# Rx_logic.net
KiCad netlist of a schematic drawn in Altium Designer
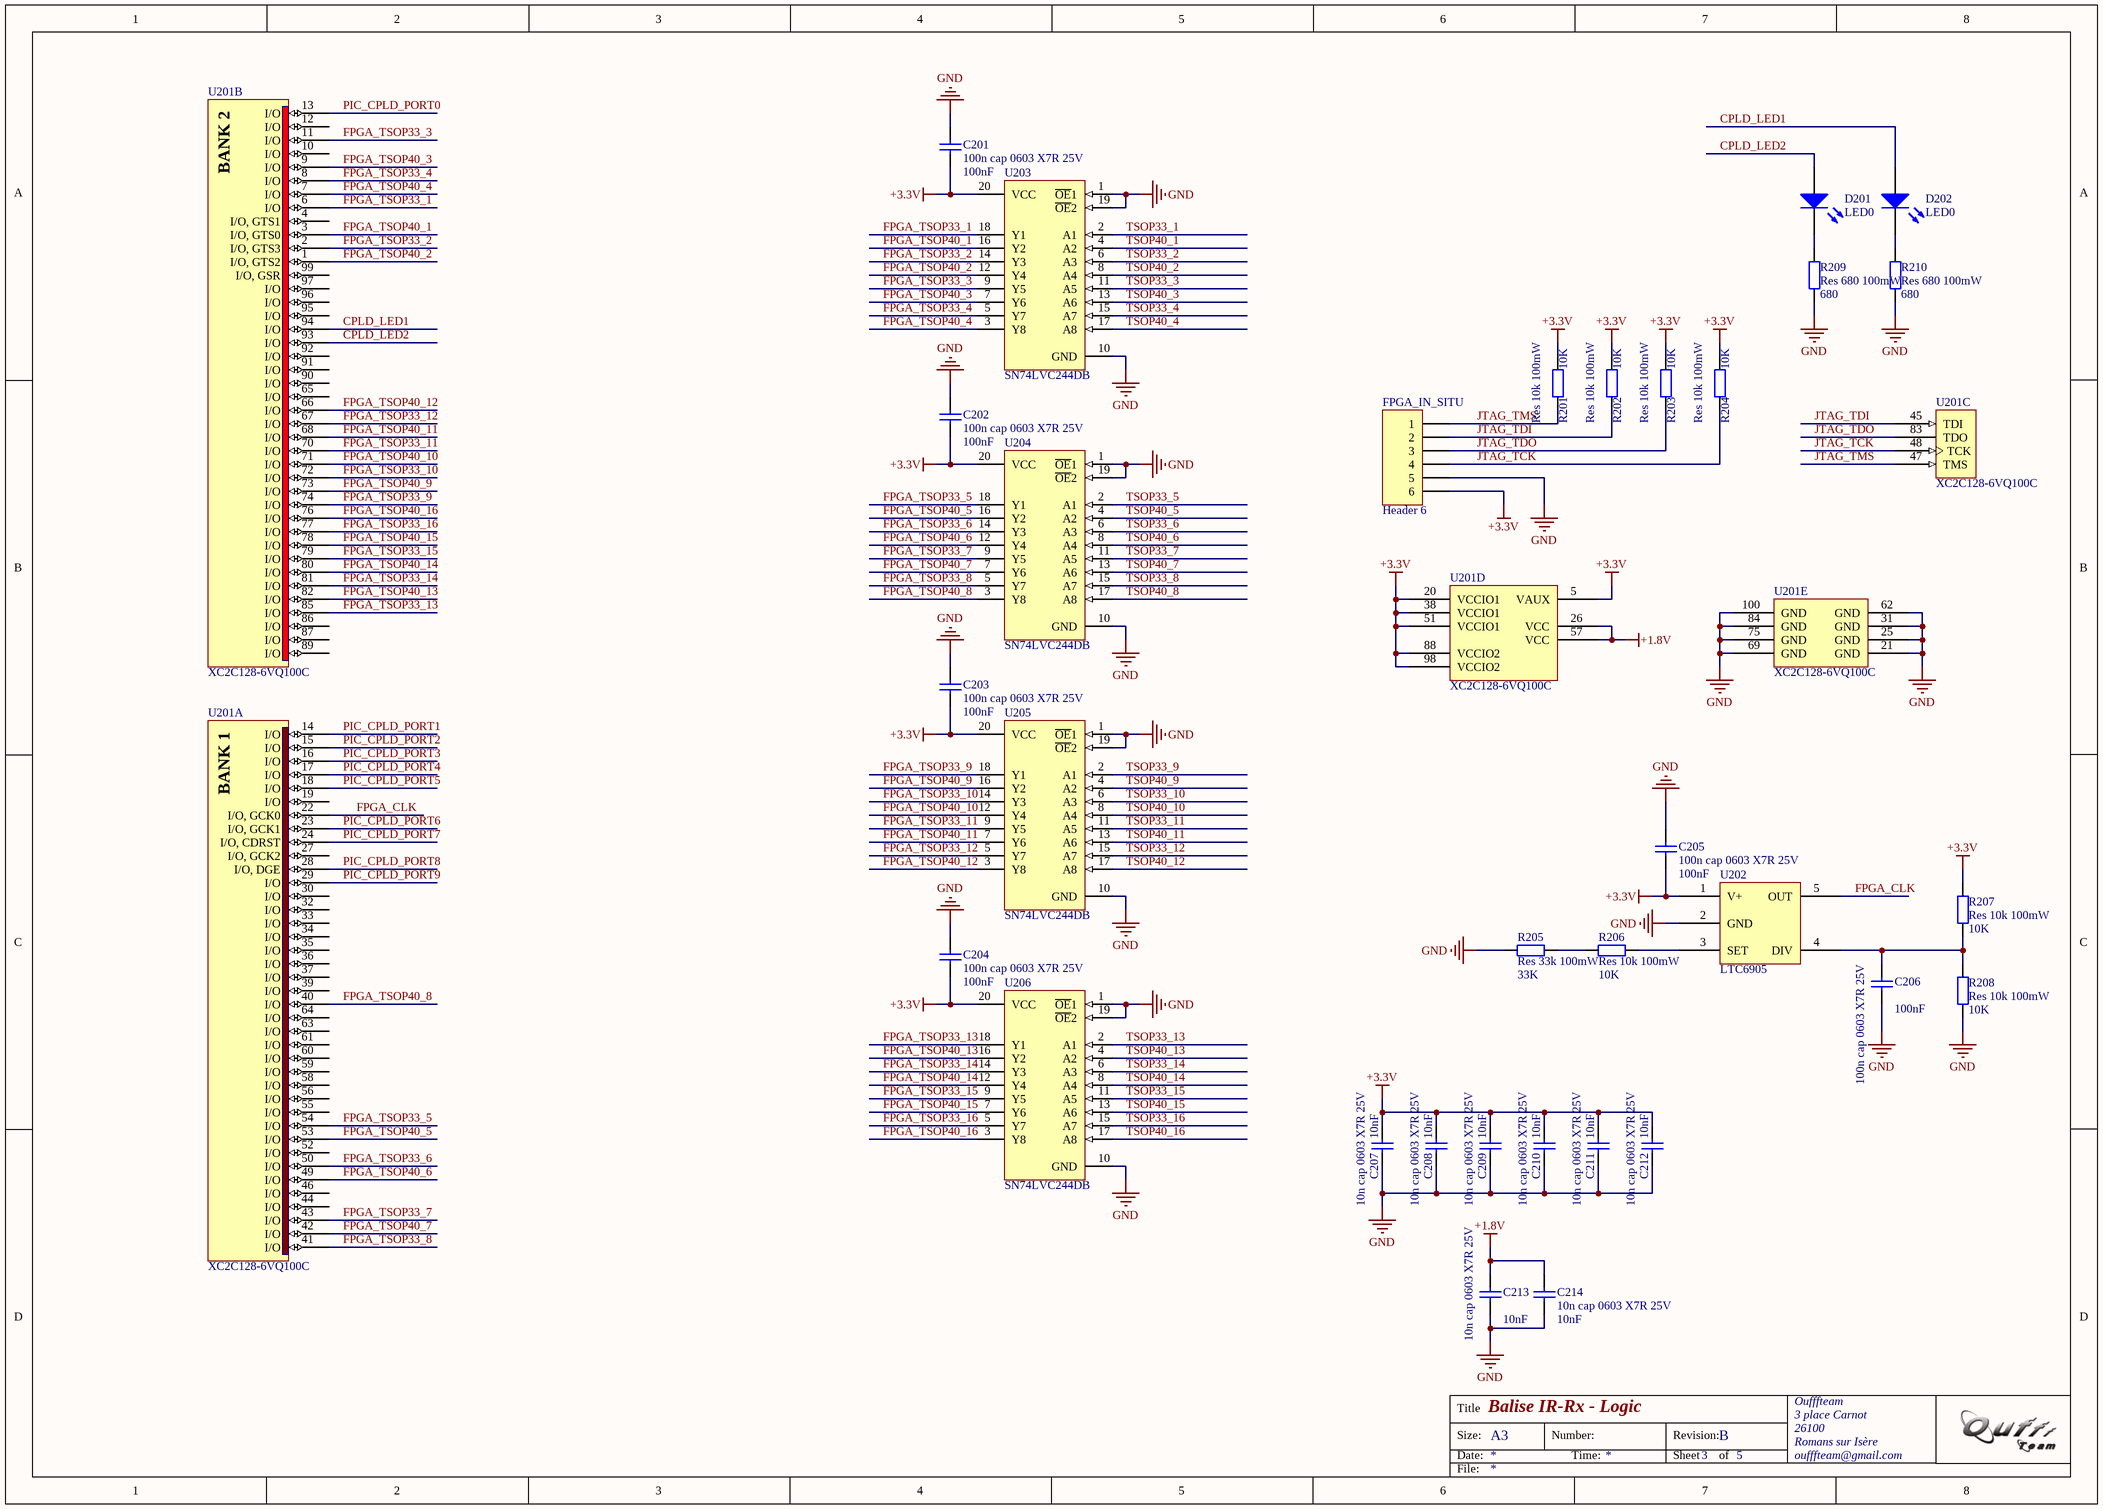
[diagram p0: Rx_logic.SchDoc]

(export (version "E")
  (design (tool "Eeschema 10.0.6"))
  (components
    (comp (ref "C201")
      (value "100n cap 0603 X7R 25V")
      (footprint "0603")
      (description "Capacitor")
      (fields (field (name "ALTIUM_VALUE") "100nF") (field (name "PUBLISHER") "Altium Limited"))
      (libsource (lib "Miscellaneous Devices") (part "Cap"))
    )
    (comp (ref "C202")
      (value "100n cap 0603 X7R 25V")
      (footprint "0603")
      (description "Capacitor")
      (fields (field (name "ALTIUM_VALUE") "100nF") (field (name "PUBLISHER") "Altium Limited"))
      (libsource (lib "Miscellaneous Devices") (part "Cap"))
    )
    (comp (ref "C203")
      (value "100n cap 0603 X7R 25V")
      (footprint "0603")
      (description "Capacitor")
      (fields (field (name "ALTIUM_VALUE") "100nF") (field (name "PUBLISHER") "Altium Limited"))
      (libsource (lib "Miscellaneous Devices") (part "Cap"))
    )
    (comp (ref "C204")
      (value "100n cap 0603 X7R 25V")
      (footprint "0603")
      (description "Capacitor")
      (fields (field (name "ALTIUM_VALUE") "100nF") (field (name "PUBLISHER") "Altium Limited"))
      (libsource (lib "Miscellaneous Devices") (part "Cap"))
    )
    (comp (ref "C205")
      (value "100n cap 0603 X7R 25V")
      (footprint "0603")
      (description "Capacitor")
      (fields (field (name "ALTIUM_VALUE") "100nF") (field (name "PUBLISHER") "Altium Limited"))
      (libsource (lib "Miscellaneous Devices") (part "Cap"))
    )
    (comp (ref "C206")
      (value "100n cap 0603 X7R 25V")
      (footprint "0603")
      (description "Capacitor")
      (fields (field (name "ALTIUM_VALUE") "100nF") (field (name "PUBLISHER") "Altium Limited"))
      (libsource (lib "Miscellaneous Devices") (part "Cap"))
    )
    (comp (ref "C207")
      (value "10n cap 0603 X7R 25V")
      (footprint "0603")
      (description "Capacitor")
      (fields (field (name "ALTIUM_VALUE") "10nF") (field (name "PUBLISHER") "Altium Limited"))
      (libsource (lib "Miscellaneous Devices") (part "Cap"))
    )
    (comp (ref "C208")
      (value "10n cap 0603 X7R 25V")
      (footprint "0603")
      (description "Capacitor")
      (fields (field (name "ALTIUM_VALUE") "10nF") (field (name "PUBLISHER") "Altium Limited"))
      (libsource (lib "Miscellaneous Devices") (part "Cap"))
    )
    (comp (ref "C209")
      (value "10n cap 0603 X7R 25V")
      (footprint "0603")
      (description "Capacitor")
      (fields (field (name "ALTIUM_VALUE") "10nF") (field (name "PUBLISHER") "Altium Limited"))
      (libsource (lib "Miscellaneous Devices") (part "Cap"))
    )
    (comp (ref "C210")
      (value "10n cap 0603 X7R 25V")
      (footprint "0603")
      (description "Capacitor")
      (fields (field (name "ALTIUM_VALUE") "10nF") (field (name "PUBLISHER") "Altium Limited"))
      (libsource (lib "Miscellaneous Devices") (part "Cap"))
    )
    (comp (ref "C211")
      (value "10n cap 0603 X7R 25V")
      (footprint "0603")
      (description "Capacitor")
      (fields (field (name "ALTIUM_VALUE") "10nF") (field (name "PUBLISHER") "Altium Limited"))
      (libsource (lib "Miscellaneous Devices") (part "Cap"))
    )
    (comp (ref "C212")
      (value "10n cap 0603 X7R 25V")
      (footprint "0603")
      (description "Capacitor")
      (fields (field (name "ALTIUM_VALUE") "10nF") (field (name "PUBLISHER") "Altium Limited"))
      (libsource (lib "Miscellaneous Devices") (part "Cap"))
    )
    (comp (ref "C213")
      (value "10n cap 0603 X7R 25V")
      (footprint "0603")
      (description "Capacitor")
      (fields (field (name "ALTIUM_VALUE") "10nF") (field (name "PUBLISHER") "Altium Limited"))
      (libsource (lib "Miscellaneous Devices") (part "Cap"))
    )
    (comp (ref "C214")
      (value "10n cap 0603 X7R 25V")
      (footprint "0603")
      (description "Capacitor")
      (fields (field (name "ALTIUM_VALUE") "10nF") (field (name "PUBLISHER") "Altium Limited"))
      (libsource (lib "Miscellaneous Devices") (part "Cap"))
    )
    (comp (ref "D201")
      (value "LED0")
      (footprint "0603")
      (description "0603 Led")
      (fields (field (name "PUBLISHER") "Altium Limited"))
      (libsource (lib "Miscellaneous Devices") (part "LED0"))
    )
    (comp (ref "D202")
      (value "LED0")
      (footprint "0603")
      (description "0603 Led")
      (fields (field (name "PUBLISHER") "Altium Limited"))
      (libsource (lib "Miscellaneous Devices") (part "LED0"))
    )
    (comp (ref "FPGA_IN_SITU")
      (value "Header 6")
      (footprint "HDR1X6")
      (description "Header, 6-Pin")
      (fields (field (name "PUBLISHER") "Altium Limited"))
      (libsource (lib "Miscellaneous Connectors") (part "Header 6"))
    )
    (comp (ref "R201")
      (value "Res 10k 100mW")
      (footprint "0603")
      (description "Resistor")
      (fields (field (name "ALTIUM_VALUE") "10K") (field (name "PUBLISHER") "Altium Limited"))
      (libsource (lib "Miscellaneous Devices") (part "Res2"))
    )
    (comp (ref "R202")
      (value "Res 10k 100mW")
      (footprint "0603")
      (description "Resistor")
      (fields (field (name "ALTIUM_VALUE") "10K") (field (name "PUBLISHER") "Altium Limited"))
      (libsource (lib "Miscellaneous Devices") (part "Res2"))
    )
    (comp (ref "R203")
      (value "Res 10k 100mW")
      (footprint "0603")
      (description "Resistor")
      (fields (field (name "ALTIUM_VALUE") "10K") (field (name "PUBLISHER") "Altium Limited"))
      (libsource (lib "Miscellaneous Devices") (part "Res2"))
    )
    (comp (ref "R204")
      (value "Res 10k 100mW")
      (footprint "0603")
      (description "Resistor")
      (fields (field (name "ALTIUM_VALUE") "10K") (field (name "PUBLISHER") "Altium Limited"))
      (libsource (lib "Miscellaneous Devices") (part "Res2"))
    )
    (comp (ref "R205")
      (value "Res 33k 100mW")
      (footprint "0603")
      (description "Resistor")
      (fields (field (name "ALTIUM_VALUE") "33K") (field (name "PUBLISHER") "Altium Limited"))
      (libsource (lib "") (part "Res2_1"))
    )
    (comp (ref "R206")
      (value "Res 10k 100mW")
      (footprint "0603")
      (description "Resistor")
      (fields (field (name "ALTIUM_VALUE") "10K") (field (name "PUBLISHER") "Altium Limited"))
      (libsource (lib "") (part "Res2_1"))
    )
    (comp (ref "R207")
      (value "Res 10k 100mW")
      (footprint "0603")
      (description "Resistor")
      (fields (field (name "ALTIUM_VALUE") "10K") (field (name "PUBLISHER") "Altium Limited"))
      (libsource (lib "Miscellaneous Devices") (part "Res2"))
    )
    (comp (ref "R208")
      (value "Res 10k 100mW")
      (footprint "0603")
      (description "Resistor")
      (fields (field (name "ALTIUM_VALUE") "10K") (field (name "PUBLISHER") "Altium Limited"))
      (libsource (lib "Miscellaneous Devices") (part "Res2"))
    )
    (comp (ref "R209")
      (value "Res 680 100mW")
      (footprint "0603")
      (description "Resistor")
      (fields (field (name "ALTIUM_VALUE") "680") (field (name "PUBLISHER") "Altium Limited"))
      (libsource (lib "") (part "Res2_2"))
    )
    (comp (ref "R210")
      (value "Res 680 100mW")
      (footprint "0603")
      (description "Resistor")
      (fields (field (name "ALTIUM_VALUE") "680") (field (name "PUBLISHER") "Altium Limited"))
      (libsource (lib "") (part "Res2_2"))
    )
    (comp (ref "U201")
      (value "XC2C128-6VQ100C")
      (footprint "VQ100_N")
      (description "CoolRunner-II, 1.8V, 128 Macrocell CPLD, 100-Pin VQFP, Commercial Grade")
      (fields (field (name "PUBLISHER") "Altium Limited"))
      (libsource (lib "Xilinx CoolRunner II") (part "XC2C128-6VQ100C"))
    )
    (comp (ref "U202")
      (value "LTC6905")
      (footprint "SOT23-5")
      (description "17MHz to 170MHz Resistor Set SOT-23 Oscillator")
      (libsource (lib "Oufff_Lib2") (part "LTC6905"))
    )
    (comp (ref "U203")
      (value "SN74LVC244DB")
      (footprint "DB020_N")
      (description "Octal Buffer/Driver with 3-State Outputs")
      (fields (field (name "PUBLISHER") "Altium Limited"))
      (libsource (lib "TI Logic Buffer Line Driver") (part "SN74LVC244DB"))
    )
    (comp (ref "U204")
      (value "SN74LVC244DB")
      (footprint "DB020_N")
      (description "Octal Buffer/Driver with 3-State Outputs")
      (fields (field (name "PUBLISHER") "Altium Limited"))
      (libsource (lib "TI Logic Buffer Line Driver") (part "SN74LVC244DB"))
    )
    (comp (ref "U205")
      (value "SN74LVC244DB")
      (footprint "DB020_N")
      (description "Octal Buffer/Driver with 3-State Outputs")
      (fields (field (name "PUBLISHER") "Altium Limited"))
      (libsource (lib "TI Logic Buffer Line Driver") (part "SN74LVC244DB"))
    )
    (comp (ref "U206")
      (value "SN74LVC244DB")
      (footprint "DB020_N")
      (description "Octal Buffer/Driver with 3-State Outputs")
      (fields (field (name "PUBLISHER") "Altium Limited"))
      (libsource (lib "TI Logic Buffer Line Driver") (part "SN74LVC244DB"))
    )
  )
  (nets
    (net (code "1") (name "+1.8V") (class "Default")
      (node (ref "C213") (pin "2") (pinfunction "2_2") (pintype "passive"))
      (node (ref "C214") (pin "2") (pinfunction "2_2") (pintype "passive"))
      (node (ref "U201") (pin "26") (pinfunction "VCC_26") (pintype "power_in"))
      (node (ref "U201") (pin "57") (pinfunction "VCC_57") (pintype "power_in"))
    )
    (net (code "2") (name "+3.3V") (class "Default")
      (node (ref "C201") (pin "1") (pinfunction "1_1") (pintype "passive"))
      (node (ref "C202") (pin "1") (pinfunction "1_1") (pintype "passive"))
      (node (ref "C203") (pin "1") (pinfunction "1_1") (pintype "passive"))
      (node (ref "C204") (pin "1") (pinfunction "1_1") (pintype "passive"))
      (node (ref "C205") (pin "1") (pinfunction "1_1") (pintype "passive"))
      (node (ref "C207") (pin "2") (pinfunction "2_2") (pintype "passive"))
      (node (ref "C208") (pin "2") (pinfunction "2_2") (pintype "passive"))
      (node (ref "C209") (pin "2") (pinfunction "2_2") (pintype "passive"))
      (node (ref "C210") (pin "2") (pinfunction "2_2") (pintype "passive"))
      (node (ref "C211") (pin "2") (pinfunction "2_2") (pintype "passive"))
      (node (ref "C212") (pin "2") (pinfunction "2_2") (pintype "passive"))
      (node (ref "FPGA_IN_SITU") (pin "6") (pinfunction "6_6") (pintype "passive"))
      (node (ref "R201") (pin "2") (pinfunction "2_2") (pintype "passive"))
      (node (ref "R202") (pin "2") (pinfunction "2_2") (pintype "passive"))
      (node (ref "R203") (pin "2") (pinfunction "2_2") (pintype "passive"))
      (node (ref "R204") (pin "2") (pinfunction "2_2") (pintype "passive"))
      (node (ref "R207") (pin "2") (pinfunction "2_2") (pintype "passive"))
      (node (ref "U201") (pin "20") (pinfunction "VCCIO1_20") (pintype "power_in"))
      (node (ref "U201") (pin "38") (pinfunction "VCCIO1_38") (pintype "power_in"))
      (node (ref "U201") (pin "5") (pinfunction "VAUX_5") (pintype "power_in"))
      (node (ref "U201") (pin "51") (pinfunction "VCCIO1_51") (pintype "power_in"))
      (node (ref "U201") (pin "88") (pinfunction "VCCIO2_88") (pintype "power_in"))
      (node (ref "U201") (pin "98") (pinfunction "VCCIO2_98") (pintype "power_in"))
      (node (ref "U202") (pin "1") (pinfunction "V+_1") (pintype "passive"))
      (node (ref "U203") (pin "20") (pinfunction "VCC_20") (pintype "power_in"))
      (node (ref "U204") (pin "20") (pinfunction "VCC_20") (pintype "power_in"))
      (node (ref "U205") (pin "20") (pinfunction "VCC_20") (pintype "power_in"))
      (node (ref "U206") (pin "20") (pinfunction "VCC_20") (pintype "power_in"))
    )
    (net (code "3") (name "/CPLD_LED1") (class "Default")
      (node (ref "D202") (pin "1") (pinfunction "A_1") (pintype "passive"))
      (node (ref "U201") (pin "94") (pinfunction "I/O_94") (pintype "bidirectional"))
    )
    (net (code "4") (name "/CPLD_LED2") (class "Default")
      (node (ref "D201") (pin "1") (pinfunction "A_1") (pintype "passive"))
      (node (ref "U201") (pin "93") (pinfunction "I/O_93") (pintype "bidirectional"))
    )
    (net (code "5") (name "/FPGA_CLK") (class "Default")
      (node (ref "U201") (pin "22") (pinfunction "I/O,_GCK0_22") (pintype "bidirectional"))
      (node (ref "U202") (pin "5") (pinfunction "OUT_5") (pintype "passive"))
    )
    (net (code "6") (name "/FPGA_TSOP33_1") (class "Default")
      (node (ref "U201") (pin "6") (pinfunction "I/O_6") (pintype "bidirectional"))
      (node (ref "U203") (pin "18") (pinfunction "Y1_18") (pintype "tri_state"))
    )
    (net (code "7") (name "/FPGA_TSOP33_2") (class "Default")
      (node (ref "U201") (pin "2") (pinfunction "I/O,_GTS3_2") (pintype "bidirectional"))
      (node (ref "U203") (pin "14") (pinfunction "Y3_14") (pintype "tri_state"))
    )
    (net (code "8") (name "/FPGA_TSOP33_3") (class "Default")
      (node (ref "U201") (pin "11") (pinfunction "I/O_11") (pintype "bidirectional"))
      (node (ref "U203") (pin "9") (pinfunction "Y5_9") (pintype "tri_state"))
    )
    (net (code "9") (name "/FPGA_TSOP33_4") (class "Default")
      (node (ref "U201") (pin "8") (pinfunction "I/O_8") (pintype "bidirectional"))
      (node (ref "U203") (pin "5") (pinfunction "Y7_5") (pintype "tri_state"))
    )
    (net (code "10") (name "/FPGA_TSOP33_5") (class "Default")
      (node (ref "U201") (pin "54") (pinfunction "I/O_54") (pintype "bidirectional"))
      (node (ref "U204") (pin "18") (pinfunction "Y1_18") (pintype "tri_state"))
    )
    (net (code "11") (name "/FPGA_TSOP33_6") (class "Default")
      (node (ref "U201") (pin "50") (pinfunction "I/O_50") (pintype "bidirectional"))
      (node (ref "U204") (pin "14") (pinfunction "Y3_14") (pintype "tri_state"))
    )
    (net (code "12") (name "/FPGA_TSOP33_7") (class "Default")
      (node (ref "U201") (pin "43") (pinfunction "I/O_43") (pintype "bidirectional"))
      (node (ref "U204") (pin "9") (pinfunction "Y5_9") (pintype "tri_state"))
    )
    (net (code "13") (name "/FPGA_TSOP33_8") (class "Default")
      (node (ref "U201") (pin "41") (pinfunction "I/O_41") (pintype "bidirectional"))
      (node (ref "U204") (pin "5") (pinfunction "Y7_5") (pintype "tri_state"))
    )
    (net (code "14") (name "/FPGA_TSOP33_9") (class "Default")
      (node (ref "U201") (pin "74") (pinfunction "I/O_74") (pintype "bidirectional"))
      (node (ref "U205") (pin "18") (pinfunction "Y1_18") (pintype "tri_state"))
    )
    (net (code "15") (name "/FPGA_TSOP33_10") (class "Default")
      (node (ref "U201") (pin "72") (pinfunction "I/O_72") (pintype "bidirectional"))
      (node (ref "U205") (pin "14") (pinfunction "Y3_14") (pintype "tri_state"))
    )
    (net (code "16") (name "/FPGA_TSOP33_11") (class "Default")
      (node (ref "U201") (pin "70") (pinfunction "I/O_70") (pintype "bidirectional"))
      (node (ref "U205") (pin "9") (pinfunction "Y5_9") (pintype "tri_state"))
    )
    (net (code "17") (name "/FPGA_TSOP33_12") (class "Default")
      (node (ref "U201") (pin "67") (pinfunction "I/O_67") (pintype "bidirectional"))
      (node (ref "U205") (pin "5") (pinfunction "Y7_5") (pintype "tri_state"))
    )
    (net (code "18") (name "/FPGA_TSOP33_13") (class "Default")
      (node (ref "U201") (pin "85") (pinfunction "I/O_85") (pintype "bidirectional"))
      (node (ref "U206") (pin "18") (pinfunction "Y1_18") (pintype "tri_state"))
    )
    (net (code "19") (name "/FPGA_TSOP33_14") (class "Default")
      (node (ref "U201") (pin "81") (pinfunction "I/O_81") (pintype "bidirectional"))
      (node (ref "U206") (pin "14") (pinfunction "Y3_14") (pintype "tri_state"))
    )
    (net (code "20") (name "/FPGA_TSOP33_15") (class "Default")
      (node (ref "U201") (pin "79") (pinfunction "I/O_79") (pintype "bidirectional"))
      (node (ref "U206") (pin "9") (pinfunction "Y5_9") (pintype "tri_state"))
    )
    (net (code "21") (name "/FPGA_TSOP33_16") (class "Default")
      (node (ref "U201") (pin "77") (pinfunction "I/O_77") (pintype "bidirectional"))
      (node (ref "U206") (pin "5") (pinfunction "Y7_5") (pintype "tri_state"))
    )
    (net (code "22") (name "/FPGA_TSOP40_1") (class "Default")
      (node (ref "U201") (pin "3") (pinfunction "I/O,_GTS0_3") (pintype "bidirectional"))
      (node (ref "U203") (pin "16") (pinfunction "Y2_16") (pintype "tri_state"))
    )
    (net (code "23") (name "/FPGA_TSOP40_2") (class "Default")
      (node (ref "U201") (pin "1") (pinfunction "I/O,_GTS2_1") (pintype "bidirectional"))
      (node (ref "U203") (pin "12") (pinfunction "Y4_12") (pintype "tri_state"))
    )
    (net (code "24") (name "/FPGA_TSOP40_3") (class "Default")
      (node (ref "U201") (pin "9") (pinfunction "I/O_9") (pintype "bidirectional"))
      (node (ref "U203") (pin "7") (pinfunction "Y6_7") (pintype "tri_state"))
    )
    (net (code "25") (name "/FPGA_TSOP40_4") (class "Default")
      (node (ref "U201") (pin "7") (pinfunction "I/O_7") (pintype "bidirectional"))
      (node (ref "U203") (pin "3") (pinfunction "Y8_3") (pintype "tri_state"))
    )
    (net (code "26") (name "/FPGA_TSOP40_5") (class "Default")
      (node (ref "U201") (pin "53") (pinfunction "I/O_53") (pintype "bidirectional"))
      (node (ref "U204") (pin "16") (pinfunction "Y2_16") (pintype "tri_state"))
    )
    (net (code "27") (name "/FPGA_TSOP40_6") (class "Default")
      (node (ref "U201") (pin "49") (pinfunction "I/O_49") (pintype "bidirectional"))
      (node (ref "U204") (pin "12") (pinfunction "Y4_12") (pintype "tri_state"))
    )
    (net (code "28") (name "/FPGA_TSOP40_7") (class "Default")
      (node (ref "U201") (pin "42") (pinfunction "I/O_42") (pintype "bidirectional"))
      (node (ref "U204") (pin "7") (pinfunction "Y6_7") (pintype "tri_state"))
    )
    (net (code "29") (name "/FPGA_TSOP40_8") (class "Default")
      (node (ref "U201") (pin "40") (pinfunction "I/O_40") (pintype "bidirectional"))
      (node (ref "U204") (pin "3") (pinfunction "Y8_3") (pintype "tri_state"))
    )
    (net (code "30") (name "/FPGA_TSOP40_9") (class "Default")
      (node (ref "U201") (pin "73") (pinfunction "I/O_73") (pintype "bidirectional"))
      (node (ref "U205") (pin "16") (pinfunction "Y2_16") (pintype "tri_state"))
    )
    (net (code "31") (name "/FPGA_TSOP40_10") (class "Default")
      (node (ref "U201") (pin "71") (pinfunction "I/O_71") (pintype "bidirectional"))
      (node (ref "U205") (pin "12") (pinfunction "Y4_12") (pintype "tri_state"))
    )
    (net (code "32") (name "/FPGA_TSOP40_11") (class "Default")
      (node (ref "U201") (pin "68") (pinfunction "I/O_68") (pintype "bidirectional"))
      (node (ref "U205") (pin "7") (pinfunction "Y6_7") (pintype "tri_state"))
    )
    (net (code "33") (name "/FPGA_TSOP40_12") (class "Default")
      (node (ref "U201") (pin "66") (pinfunction "I/O_66") (pintype "bidirectional"))
      (node (ref "U205") (pin "3") (pinfunction "Y8_3") (pintype "tri_state"))
    )
    (net (code "34") (name "/FPGA_TSOP40_13") (class "Default")
      (node (ref "U201") (pin "82") (pinfunction "I/O_82") (pintype "bidirectional"))
      (node (ref "U206") (pin "16") (pinfunction "Y2_16") (pintype "tri_state"))
    )
    (net (code "35") (name "/FPGA_TSOP40_14") (class "Default")
      (node (ref "U201") (pin "80") (pinfunction "I/O_80") (pintype "bidirectional"))
      (node (ref "U206") (pin "12") (pinfunction "Y4_12") (pintype "tri_state"))
    )
    (net (code "36") (name "/FPGA_TSOP40_15") (class "Default")
      (node (ref "U201") (pin "78") (pinfunction "I/O_78") (pintype "bidirectional"))
      (node (ref "U206") (pin "7") (pinfunction "Y6_7") (pintype "tri_state"))
    )
    (net (code "37") (name "/FPGA_TSOP40_16") (class "Default")
      (node (ref "U201") (pin "76") (pinfunction "I/O_76") (pintype "bidirectional"))
      (node (ref "U206") (pin "3") (pinfunction "Y8_3") (pintype "tri_state"))
    )
    (net (code "38") (name "/JTAG_TCK") (class "Default")
      (node (ref "FPGA_IN_SITU") (pin "4") (pinfunction "4_4") (pintype "passive"))
      (node (ref "R204") (pin "1") (pinfunction "1_1") (pintype "passive"))
      (node (ref "U201") (pin "48") (pinfunction "TCK_48") (pintype "input"))
    )
    (net (code "39") (name "/JTAG_TDI") (class "Default")
      (node (ref "FPGA_IN_SITU") (pin "2") (pinfunction "2_2") (pintype "passive"))
      (node (ref "R202") (pin "1") (pinfunction "1_1") (pintype "passive"))
      (node (ref "U201") (pin "45") (pinfunction "TDI_45") (pintype "input"))
    )
    (net (code "40") (name "/JTAG_TDO") (class "Default")
      (node (ref "FPGA_IN_SITU") (pin "3") (pinfunction "3_3") (pintype "passive"))
      (node (ref "R203") (pin "1") (pinfunction "1_1") (pintype "passive"))
      (node (ref "U201") (pin "83") (pinfunction "TDO_83") (pintype "passive"))
    )
    (net (code "41") (name "/JTAG_TMS") (class "Default")
      (node (ref "FPGA_IN_SITU") (pin "1") (pinfunction "1_1") (pintype "passive"))
      (node (ref "R201") (pin "1") (pinfunction "1_1") (pintype "passive"))
      (node (ref "U201") (pin "47") (pinfunction "TMS_47") (pintype "input"))
    )
    (net (code "42") (name "/PIC_CPLD_PORT0") (class "Default")
      (node (ref "U201") (pin "13") (pinfunction "I/O_13") (pintype "bidirectional"))
    )
    (net (code "43") (name "/PIC_CPLD_PORT1") (class "Default")
      (node (ref "U201") (pin "14") (pinfunction "I/O_14") (pintype "bidirectional"))
    )
    (net (code "44") (name "/PIC_CPLD_PORT2") (class "Default")
      (node (ref "U201") (pin "15") (pinfunction "I/O_15") (pintype "bidirectional"))
    )
    (net (code "45") (name "/PIC_CPLD_PORT3") (class "Default")
      (node (ref "U201") (pin "16") (pinfunction "I/O_16") (pintype "bidirectional"))
    )
    (net (code "46") (name "/PIC_CPLD_PORT4") (class "Default")
      (node (ref "U201") (pin "17") (pinfunction "I/O_17") (pintype "bidirectional"))
    )
    (net (code "47") (name "/PIC_CPLD_PORT5") (class "Default")
      (node (ref "U201") (pin "18") (pinfunction "I/O_18") (pintype "bidirectional"))
    )
    (net (code "48") (name "/PIC_CPLD_PORT6") (class "Default")
      (node (ref "U201") (pin "23") (pinfunction "I/O,_GCK1_23") (pintype "bidirectional"))
    )
    (net (code "49") (name "/PIC_CPLD_PORT7") (class "Default")
      (node (ref "U201") (pin "24") (pinfunction "I/O,_CDRST_24") (pintype "bidirectional"))
    )
    (net (code "50") (name "/PIC_CPLD_PORT8") (class "Default")
      (node (ref "U201") (pin "28") (pinfunction "I/O,_DGE_28") (pintype "bidirectional"))
    )
    (net (code "51") (name "/PIC_CPLD_PORT9") (class "Default")
      (node (ref "U201") (pin "29") (pinfunction "I/O_29") (pintype "bidirectional"))
    )
    (net (code "52") (name "/TSOP33_1") (class "Default")
      (node (ref "U203") (pin "2") (pinfunction "A1_2") (pintype "input"))
    )
    (net (code "53") (name "/TSOP33_2") (class "Default")
      (node (ref "U203") (pin "6") (pinfunction "A3_6") (pintype "input"))
    )
    (net (code "54") (name "/TSOP33_3") (class "Default")
      (node (ref "U203") (pin "11") (pinfunction "A5_11") (pintype "input"))
    )
    (net (code "55") (name "/TSOP33_4") (class "Default")
      (node (ref "U203") (pin "15") (pinfunction "A7_15") (pintype "input"))
    )
    (net (code "56") (name "/TSOP33_5") (class "Default")
      (node (ref "U204") (pin "2") (pinfunction "A1_2") (pintype "input"))
    )
    (net (code "57") (name "/TSOP33_6") (class "Default")
      (node (ref "U204") (pin "6") (pinfunction "A3_6") (pintype "input"))
    )
    (net (code "58") (name "/TSOP33_7") (class "Default")
      (node (ref "U204") (pin "11") (pinfunction "A5_11") (pintype "input"))
    )
    (net (code "59") (name "/TSOP33_8") (class "Default")
      (node (ref "U204") (pin "15") (pinfunction "A7_15") (pintype "input"))
    )
    (net (code "60") (name "/TSOP33_9") (class "Default")
      (node (ref "U205") (pin "2") (pinfunction "A1_2") (pintype "input"))
    )
    (net (code "61") (name "/TSOP33_10") (class "Default")
      (node (ref "U205") (pin "6") (pinfunction "A3_6") (pintype "input"))
    )
    (net (code "62") (name "/TSOP33_11") (class "Default")
      (node (ref "U205") (pin "11") (pinfunction "A5_11") (pintype "input"))
    )
    (net (code "63") (name "/TSOP33_12") (class "Default")
      (node (ref "U205") (pin "15") (pinfunction "A7_15") (pintype "input"))
    )
    (net (code "64") (name "/TSOP33_13") (class "Default")
      (node (ref "U206") (pin "2") (pinfunction "A1_2") (pintype "input"))
    )
    (net (code "65") (name "/TSOP33_14") (class "Default")
      (node (ref "U206") (pin "6") (pinfunction "A3_6") (pintype "input"))
    )
    (net (code "66") (name "/TSOP33_15") (class "Default")
      (node (ref "U206") (pin "11") (pinfunction "A5_11") (pintype "input"))
    )
    (net (code "67") (name "/TSOP33_16") (class "Default")
      (node (ref "U206") (pin "15") (pinfunction "A7_15") (pintype "input"))
    )
    (net (code "68") (name "/TSOP40_1") (class "Default")
      (node (ref "U203") (pin "4") (pinfunction "A2_4") (pintype "input"))
    )
    (net (code "69") (name "/TSOP40_2") (class "Default")
      (node (ref "U203") (pin "8") (pinfunction "A4_8") (pintype "input"))
    )
    (net (code "70") (name "/TSOP40_3") (class "Default")
      (node (ref "U203") (pin "13") (pinfunction "A6_13") (pintype "input"))
    )
    (net (code "71") (name "/TSOP40_4") (class "Default")
      (node (ref "U203") (pin "17") (pinfunction "A8_17") (pintype "input"))
    )
    (net (code "72") (name "/TSOP40_5") (class "Default")
      (node (ref "U204") (pin "4") (pinfunction "A2_4") (pintype "input"))
    )
    (net (code "73") (name "/TSOP40_6") (class "Default")
      (node (ref "U204") (pin "8") (pinfunction "A4_8") (pintype "input"))
    )
    (net (code "74") (name "/TSOP40_7") (class "Default")
      (node (ref "U204") (pin "13") (pinfunction "A6_13") (pintype "input"))
    )
    (net (code "75") (name "/TSOP40_8") (class "Default")
      (node (ref "U204") (pin "17") (pinfunction "A8_17") (pintype "input"))
    )
    (net (code "76") (name "/TSOP40_9") (class "Default")
      (node (ref "U205") (pin "4") (pinfunction "A2_4") (pintype "input"))
    )
    (net (code "77") (name "/TSOP40_10") (class "Default")
      (node (ref "U205") (pin "8") (pinfunction "A4_8") (pintype "input"))
    )
    (net (code "78") (name "/TSOP40_11") (class "Default")
      (node (ref "U205") (pin "13") (pinfunction "A6_13") (pintype "input"))
    )
    (net (code "79") (name "/TSOP40_12") (class "Default")
      (node (ref "U205") (pin "17") (pinfunction "A8_17") (pintype "input"))
    )
    (net (code "80") (name "/TSOP40_13") (class "Default")
      (node (ref "U206") (pin "4") (pinfunction "A2_4") (pintype "input"))
    )
    (net (code "81") (name "/TSOP40_14") (class "Default")
      (node (ref "U206") (pin "8") (pinfunction "A4_8") (pintype "input"))
    )
    (net (code "82") (name "/TSOP40_15") (class "Default")
      (node (ref "U206") (pin "13") (pinfunction "A6_13") (pintype "input"))
    )
    (net (code "83") (name "/TSOP40_16") (class "Default")
      (node (ref "U206") (pin "17") (pinfunction "A8_17") (pintype "input"))
    )
    (net (code "84") (name "GND") (class "Default")
      (node (ref "C201") (pin "2") (pinfunction "2_2") (pintype "passive"))
      (node (ref "C202") (pin "2") (pinfunction "2_2") (pintype "passive"))
      (node (ref "C203") (pin "2") (pinfunction "2_2") (pintype "passive"))
      (node (ref "C204") (pin "2") (pinfunction "2_2") (pintype "passive"))
      (node (ref "C205") (pin "2") (pinfunction "2_2") (pintype "passive"))
      (node (ref "C206") (pin "1") (pinfunction "1_1") (pintype "passive"))
      (node (ref "C207") (pin "1") (pinfunction "1_1") (pintype "passive"))
      (node (ref "C208") (pin "1") (pinfunction "1_1") (pintype "passive"))
      (node (ref "C209") (pin "1") (pinfunction "1_1") (pintype "passive"))
      (node (ref "C210") (pin "1") (pinfunction "1_1") (pintype "passive"))
      (node (ref "C211") (pin "1") (pinfunction "1_1") (pintype "passive"))
      (node (ref "C212") (pin "1") (pinfunction "1_1") (pintype "passive"))
      (node (ref "C213") (pin "1") (pinfunction "1_1") (pintype "passive"))
      (node (ref "C214") (pin "1") (pinfunction "1_1") (pintype "passive"))
      (node (ref "FPGA_IN_SITU") (pin "5") (pinfunction "5_5") (pintype "passive"))
      (node (ref "R205") (pin "1") (pinfunction "1_1") (pintype "passive"))
      (node (ref "R208") (pin "1") (pinfunction "1_1") (pintype "passive"))
      (node (ref "R209") (pin "2") (pinfunction "2_2") (pintype "passive"))
      (node (ref "R210") (pin "2") (pinfunction "2_2") (pintype "passive"))
      (node (ref "U201") (pin "100") (pinfunction "GND_100") (pintype "power_in"))
      (node (ref "U201") (pin "21") (pinfunction "GND_21") (pintype "power_in"))
      (node (ref "U201") (pin "25") (pinfunction "GND_25") (pintype "power_in"))
      (node (ref "U201") (pin "31") (pinfunction "GND_31") (pintype "power_in"))
      (node (ref "U201") (pin "62") (pinfunction "GND_62") (pintype "power_in"))
      (node (ref "U201") (pin "69") (pinfunction "GND_69") (pintype "power_in"))
      (node (ref "U201") (pin "75") (pinfunction "GND_75") (pintype "power_in"))
      (node (ref "U201") (pin "84") (pinfunction "GND_84") (pintype "power_in"))
      (node (ref "U202") (pin "2") (pinfunction "GND_2") (pintype "passive"))
      (node (ref "U203") (pin "1") (pinfunction "~{OE}1_1") (pintype "input"))
      (node (ref "U203") (pin "10") (pinfunction "GND_10") (pintype "power_in"))
      (node (ref "U203") (pin "19") (pinfunction "~{OE}2_19") (pintype "input"))
      (node (ref "U204") (pin "1") (pinfunction "~{OE}1_1") (pintype "input"))
      (node (ref "U204") (pin "10") (pinfunction "GND_10") (pintype "power_in"))
      (node (ref "U204") (pin "19") (pinfunction "~{OE}2_19") (pintype "input"))
      (node (ref "U205") (pin "1") (pinfunction "~{OE}1_1") (pintype "input"))
      (node (ref "U205") (pin "10") (pinfunction "GND_10") (pintype "power_in"))
      (node (ref "U205") (pin "19") (pinfunction "~{OE}2_19") (pintype "input"))
      (node (ref "U206") (pin "1") (pinfunction "~{OE}1_1") (pintype "input"))
      (node (ref "U206") (pin "10") (pinfunction "GND_10") (pintype "power_in"))
      (node (ref "U206") (pin "19") (pinfunction "~{OE}2_19") (pintype "input"))
    )
    (net (code "85") (name "Net-(D201-K)") (class "Default")
      (node (ref "D201") (pin "2") (pinfunction "K_2") (pintype "passive"))
      (node (ref "R209") (pin "1") (pinfunction "1_1") (pintype "passive"))
    )
    (net (code "86") (name "Net-(D202-K)") (class "Default")
      (node (ref "D202") (pin "2") (pinfunction "K_2") (pintype "passive"))
      (node (ref "R210") (pin "1") (pinfunction "1_1") (pintype "passive"))
    )
    (net (code "87") (name "Net-(R205-Pad2)") (class "Default")
      (node (ref "R205") (pin "2") (pinfunction "2_2") (pintype "passive"))
      (node (ref "R206") (pin "1") (pinfunction "1_1") (pintype "passive"))
    )
    (net (code "88") (name "Net-(U202-DIV)") (class "Default")
      (node (ref "C206") (pin "2") (pinfunction "2_2") (pintype "passive"))
      (node (ref "R207") (pin "1") (pinfunction "1_1") (pintype "passive"))
      (node (ref "R208") (pin "2") (pinfunction "2_2") (pintype "passive"))
      (node (ref "U202") (pin "4") (pinfunction "DIV_4") (pintype "passive"))
    )
    (net (code "89") (name "Net-(U202-SET)") (class "Default")
      (node (ref "R206") (pin "2") (pinfunction "2_2") (pintype "passive"))
      (node (ref "U202") (pin "3") (pinfunction "SET_3") (pintype "passive"))
    )
    (net (code "90") (name "unconnected-(U201A-I{slash}O,_GCK2-Pad27)") (class "Default")
      (node (ref "U201") (pin "27") (pinfunction "I/O,_GCK2_27") (pintype "bidirectional"))
    )
    (net (code "91") (name "unconnected-(U201A-I{slash}O-Pad19)") (class "Default")
      (node (ref "U201") (pin "19") (pinfunction "I/O_19") (pintype "bidirectional"))
    )
    (net (code "92") (name "unconnected-(U201A-I{slash}O-Pad30)") (class "Default")
      (node (ref "U201") (pin "30") (pinfunction "I/O_30") (pintype "bidirectional"))
    )
    (net (code "93") (name "unconnected-(U201A-I{slash}O-Pad32)") (class "Default")
      (node (ref "U201") (pin "32") (pinfunction "I/O_32") (pintype "bidirectional"))
    )
    (net (code "94") (name "unconnected-(U201A-I{slash}O-Pad33)") (class "Default")
      (node (ref "U201") (pin "33") (pinfunction "I/O_33") (pintype "bidirectional"))
    )
    (net (code "95") (name "unconnected-(U201A-I{slash}O-Pad34)") (class "Default")
      (node (ref "U201") (pin "34") (pinfunction "I/O_34") (pintype "bidirectional"))
    )
    (net (code "96") (name "unconnected-(U201A-I{slash}O-Pad35)") (class "Default")
      (node (ref "U201") (pin "35") (pinfunction "I/O_35") (pintype "bidirectional"))
    )
    (net (code "97") (name "unconnected-(U201A-I{slash}O-Pad36)") (class "Default")
      (node (ref "U201") (pin "36") (pinfunction "I/O_36") (pintype "bidirectional"))
    )
    (net (code "98") (name "unconnected-(U201A-I{slash}O-Pad37)") (class "Default")
      (node (ref "U201") (pin "37") (pinfunction "I/O_37") (pintype "bidirectional"))
    )
    (net (code "99") (name "unconnected-(U201A-I{slash}O-Pad39)") (class "Default")
      (node (ref "U201") (pin "39") (pinfunction "I/O_39") (pintype "bidirectional"))
    )
    (net (code "100") (name "unconnected-(U201A-I{slash}O-Pad44)") (class "Default")
      (node (ref "U201") (pin "44") (pinfunction "I/O_44") (pintype "bidirectional"))
    )
    (net (code "101") (name "unconnected-(U201A-I{slash}O-Pad46)") (class "Default")
      (node (ref "U201") (pin "46") (pinfunction "I/O_46") (pintype "bidirectional"))
    )
    (net (code "102") (name "unconnected-(U201A-I{slash}O-Pad52)") (class "Default")
      (node (ref "U201") (pin "52") (pinfunction "I/O_52") (pintype "bidirectional"))
    )
    (net (code "103") (name "unconnected-(U201A-I{slash}O-Pad55)") (class "Default")
      (node (ref "U201") (pin "55") (pinfunction "I/O_55") (pintype "bidirectional"))
    )
    (net (code "104") (name "unconnected-(U201A-I{slash}O-Pad56)") (class "Default")
      (node (ref "U201") (pin "56") (pinfunction "I/O_56") (pintype "bidirectional"))
    )
    (net (code "105") (name "unconnected-(U201A-I{slash}O-Pad58)") (class "Default")
      (node (ref "U201") (pin "58") (pinfunction "I/O_58") (pintype "bidirectional"))
    )
    (net (code "106") (name "unconnected-(U201A-I{slash}O-Pad59)") (class "Default")
      (node (ref "U201") (pin "59") (pinfunction "I/O_59") (pintype "bidirectional"))
    )
    (net (code "107") (name "unconnected-(U201A-I{slash}O-Pad60)") (class "Default")
      (node (ref "U201") (pin "60") (pinfunction "I/O_60") (pintype "bidirectional"))
    )
    (net (code "108") (name "unconnected-(U201A-I{slash}O-Pad61)") (class "Default")
      (node (ref "U201") (pin "61") (pinfunction "I/O_61") (pintype "bidirectional"))
    )
    (net (code "109") (name "unconnected-(U201A-I{slash}O-Pad63)") (class "Default")
      (node (ref "U201") (pin "63") (pinfunction "I/O_63") (pintype "bidirectional"))
    )
    (net (code "110") (name "unconnected-(U201A-I{slash}O-Pad64)") (class "Default")
      (node (ref "U201") (pin "64") (pinfunction "I/O_64") (pintype "bidirectional"))
    )
    (net (code "111") (name "unconnected-(U201B-I{slash}O,_GSR-Pad99)") (class "Default")
      (node (ref "U201") (pin "99") (pinfunction "I/O,_GSR_99") (pintype "bidirectional"))
    )
    (net (code "112") (name "unconnected-(U201B-I{slash}O,_GTS1-Pad4)") (class "Default")
      (node (ref "U201") (pin "4") (pinfunction "I/O,_GTS1_4") (pintype "bidirectional"))
    )
    (net (code "113") (name "unconnected-(U201B-I{slash}O-Pad10)") (class "Default")
      (node (ref "U201") (pin "10") (pinfunction "I/O_10") (pintype "bidirectional"))
    )
    (net (code "114") (name "unconnected-(U201B-I{slash}O-Pad12)") (class "Default")
      (node (ref "U201") (pin "12") (pinfunction "I/O_12") (pintype "bidirectional"))
    )
    (net (code "115") (name "unconnected-(U201B-I{slash}O-Pad65)") (class "Default")
      (node (ref "U201") (pin "65") (pinfunction "I/O_65") (pintype "bidirectional"))
    )
    (net (code "116") (name "unconnected-(U201B-I{slash}O-Pad86)") (class "Default")
      (node (ref "U201") (pin "86") (pinfunction "I/O_86") (pintype "bidirectional"))
    )
    (net (code "117") (name "unconnected-(U201B-I{slash}O-Pad87)") (class "Default")
      (node (ref "U201") (pin "87") (pinfunction "I/O_87") (pintype "bidirectional"))
    )
    (net (code "118") (name "unconnected-(U201B-I{slash}O-Pad89)") (class "Default")
      (node (ref "U201") (pin "89") (pinfunction "I/O_89") (pintype "bidirectional"))
    )
    (net (code "119") (name "unconnected-(U201B-I{slash}O-Pad90)") (class "Default")
      (node (ref "U201") (pin "90") (pinfunction "I/O_90") (pintype "bidirectional"))
    )
    (net (code "120") (name "unconnected-(U201B-I{slash}O-Pad91)") (class "Default")
      (node (ref "U201") (pin "91") (pinfunction "I/O_91") (pintype "bidirectional"))
    )
    (net (code "121") (name "unconnected-(U201B-I{slash}O-Pad92)") (class "Default")
      (node (ref "U201") (pin "92") (pinfunction "I/O_92") (pintype "bidirectional"))
    )
    (net (code "122") (name "unconnected-(U201B-I{slash}O-Pad95)") (class "Default")
      (node (ref "U201") (pin "95") (pinfunction "I/O_95") (pintype "bidirectional"))
    )
    (net (code "123") (name "unconnected-(U201B-I{slash}O-Pad96)") (class "Default")
      (node (ref "U201") (pin "96") (pinfunction "I/O_96") (pintype "bidirectional"))
    )
    (net (code "124") (name "unconnected-(U201B-I{slash}O-Pad97)") (class "Default")
      (node (ref "U201") (pin "97") (pinfunction "I/O_97") (pintype "bidirectional"))
    )
  )
)
